# ESP_Client.net
KiCad netlist of a schematic drawn in EasyEDA
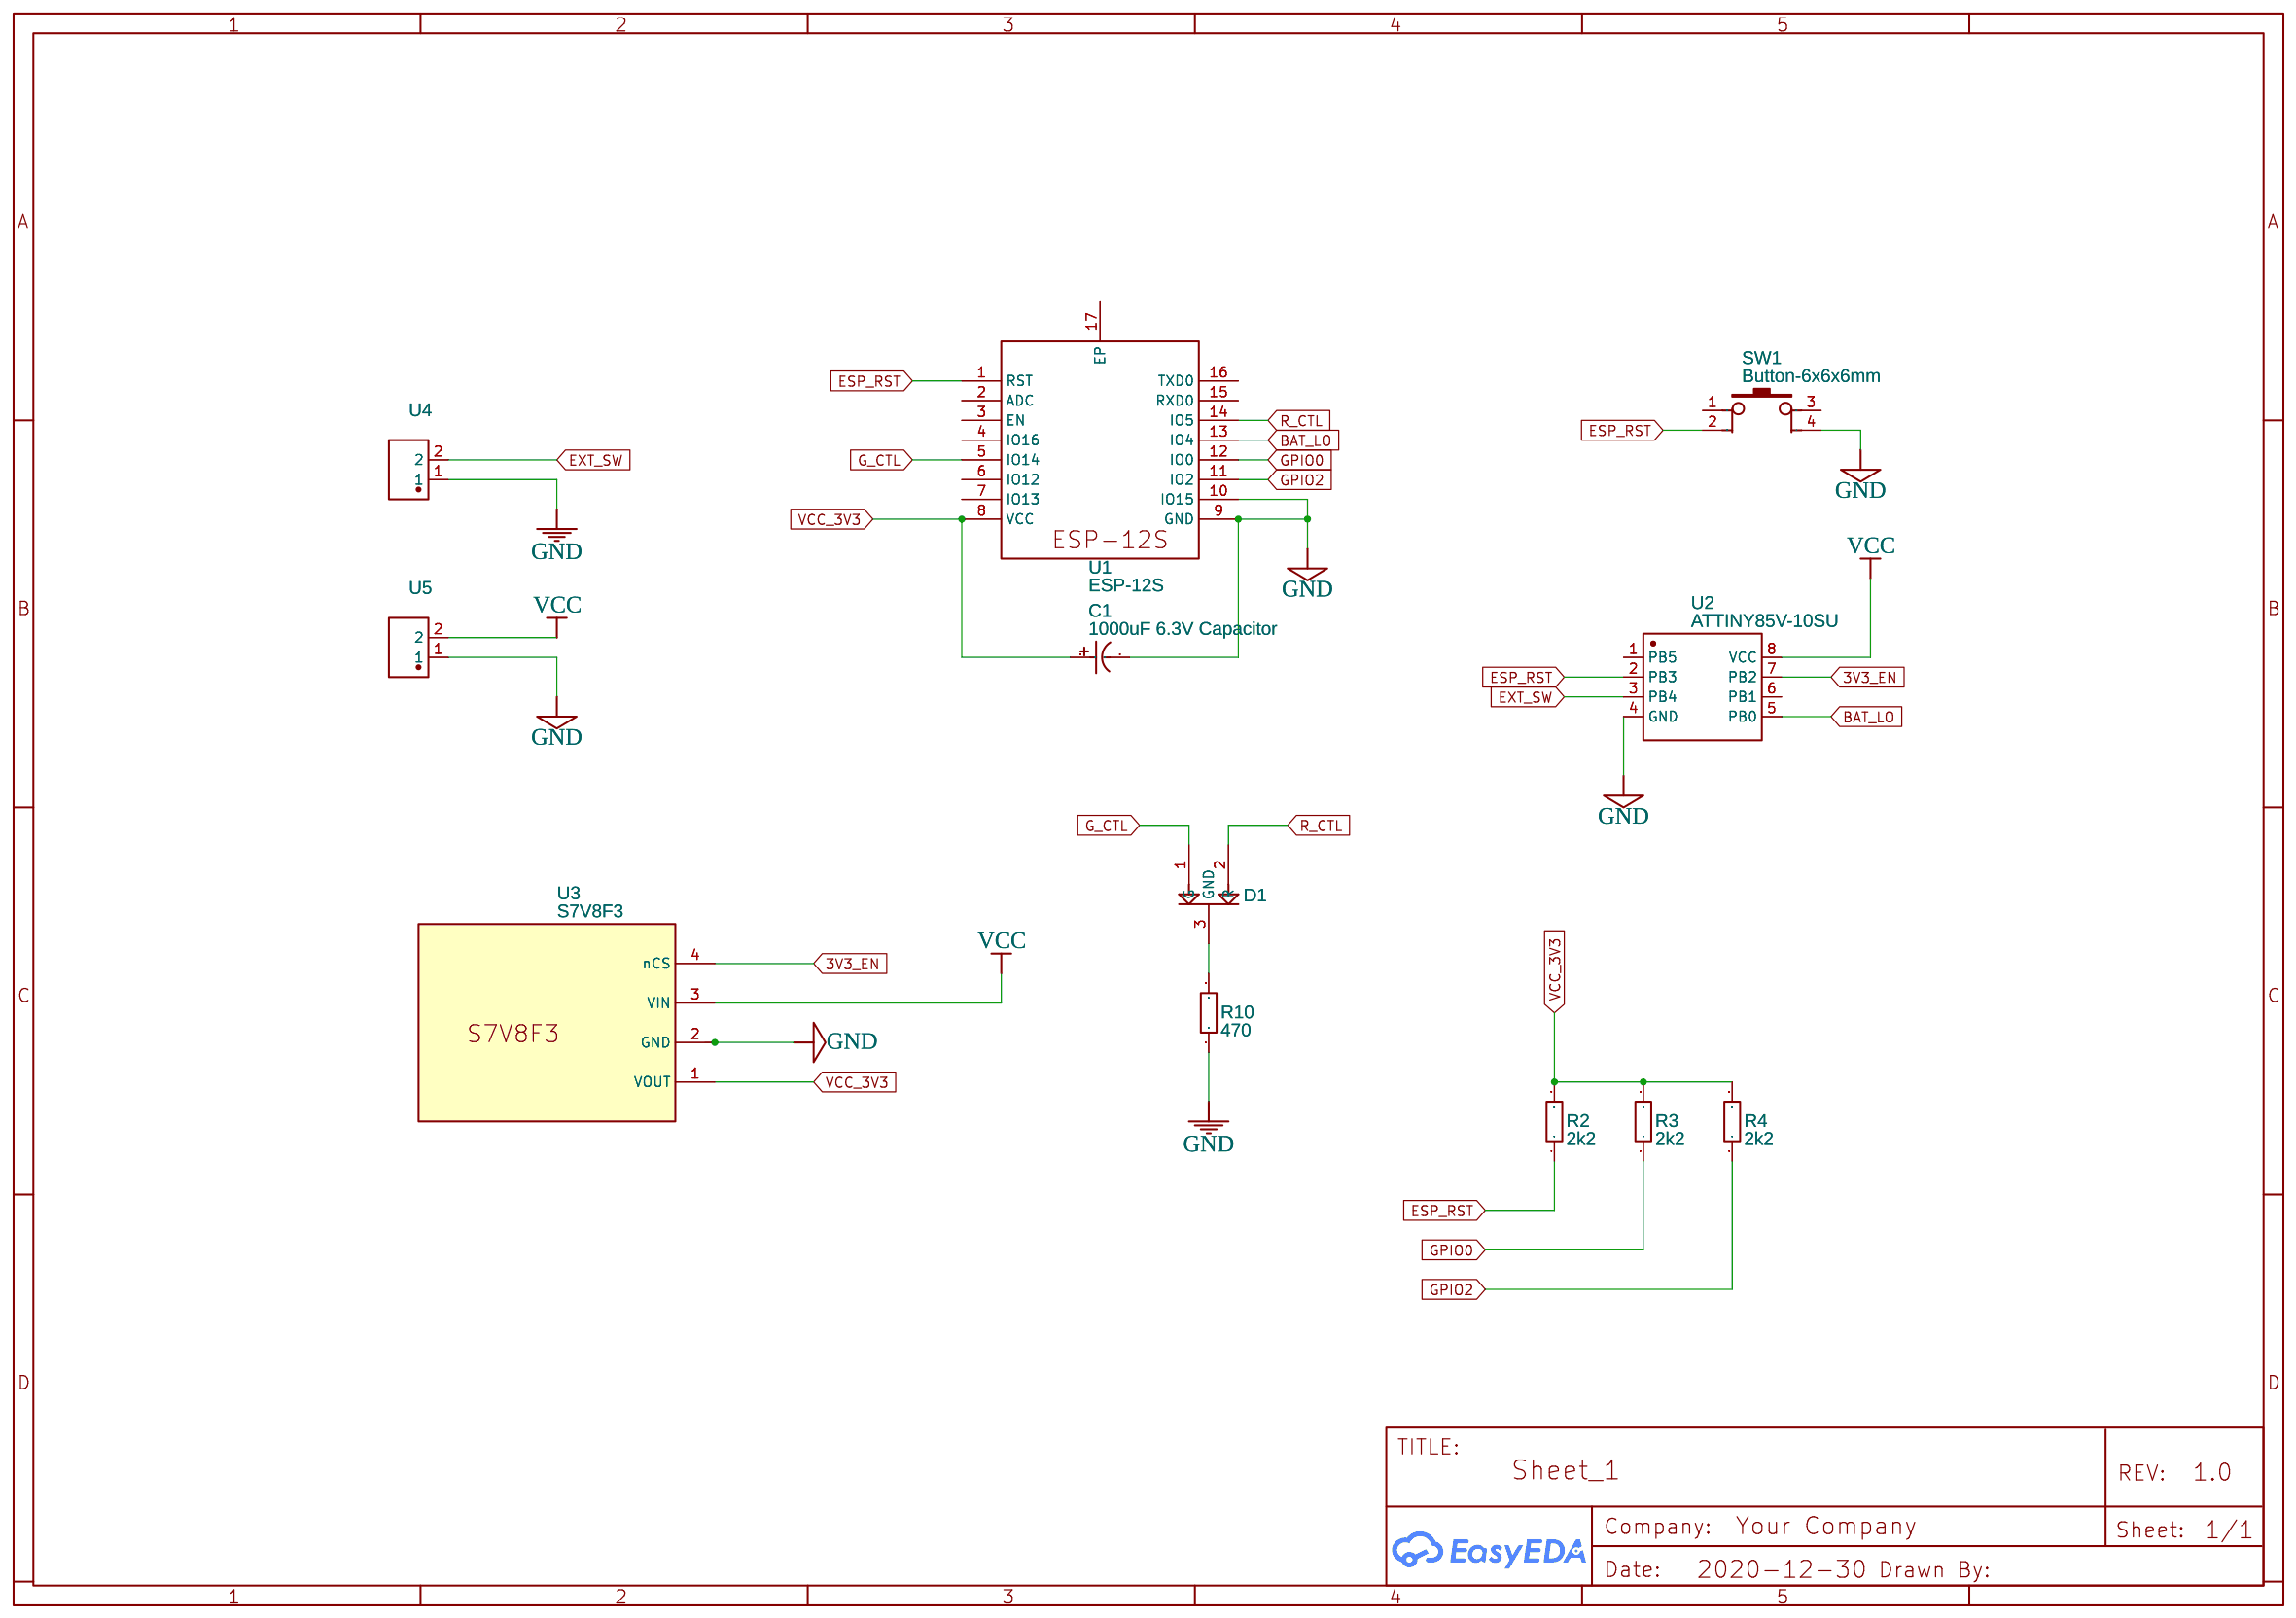
[diagram p0: schematic sheet]

(export (version "E")
  (design (tool "Eeschema 10.0.6"))
  (components
    (comp (ref "C1") (value "1000uF 6.3V Capacitor") (libsource (lib "") (part "1000uF 6.3V Capacitor")))
    (comp (ref "D1")
      (value "RED GREEN CATODO")
      (fields (field (name "BOM_Manufacturer Part") "RG309WK-C"))
      (libsource (lib "") (part "RED GREEN CATODO"))
    )
    (comp (ref "R2")
      (value "2k2")
      (fields
        (field (name "BOM_Manufacturer Part") "CFR02SJ0220A10")
        (field (name "BOM_Supplier Part") "C69874")
      )
      (libsource (lib "") (part "2k2"))
    )
    (comp (ref "R3")
      (value "2k2")
      (fields
        (field (name "BOM_Manufacturer Part") "CFR02SJ0220A10")
        (field (name "BOM_Supplier Part") "C69874")
      )
      (libsource (lib "") (part "2k2"))
    )
    (comp (ref "R4")
      (value "2k2")
      (fields
        (field (name "BOM_Manufacturer Part") "CFR02SJ0220A10")
        (field (name "BOM_Supplier Part") "C69874")
      )
      (libsource (lib "") (part "2k2"))
    )
    (comp (ref "R10")
      (value "470")
      (fields
        (field (name "BOM_Manufacturer Part") "MFR0W4F4700A50")
        (field (name "BOM_Supplier Part") "C58592")
      )
      (libsource (lib "") (part "47Ω"))
    )
    (comp (ref "SW1")
      (value "Button-6x6x6mm")
      (fields
        (field (name "BOM_Manufacturer Part") "Switch,6*6*6Plastic head,260G, 0.25mm,Straight line")
        (field (name "BOM_Supplier Part") "C71836")
      )
      (libsource (lib "") (part "Button-6x6x6mm"))
    )
    (comp (ref "U1")
      (value "ESP-12S")
      (fields (field (name "BOM_Supplier Part") "C82898"))
      (libsource (lib "") (part "ESP-12S"))
    )
    (comp (ref "U2")
      (value "ATTINY85V-10SU")
      (fields (field (name "BOM_Supplier Part") "C152192"))
      (libsource (lib "") (part "ATTINY85V-10SU"))
    )
    (comp (ref "U3") (value "S7V8F3") (libsource (lib "") (part "S7V8F3")))
    (comp (ref "U4")
      (value "XY301V-A-5.0-2P")
      (fields (field (name "BOM_Supplier Part") "C557651"))
      (libsource (lib "") (part "XY301V-A-5.0-2P"))
    )
    (comp (ref "U5")
      (value "XY301V-A-5.0-2P")
      (fields (field (name "BOM_Supplier Part") "C557651"))
      (libsource (lib "") (part "XY301V-A-5.0-2P"))
    )
  )
  (nets
    (net (code "1") (name "3V3_EN") (class "Default")
      (node (ref "U2") (pin "7") (pinfunction "PB2_7") (pintype "unspecified"))
      (node (ref "U3") (pin "4") (pinfunction "nCS_4") (pintype "unspecified"))
    )
    (net (code "2") (name "BAT_LO") (class "Default")
      (node (ref "U1") (pin "13") (pinfunction "IO4_13") (pintype "unspecified"))
      (node (ref "U2") (pin "5") (pinfunction "PB0_5") (pintype "unspecified"))
    )
    (net (code "3") (name "ESP_RST") (class "Default")
      (node (ref "R2") (pin "1") (pinfunction "1_1") (pintype "input"))
      (node (ref "SW1") (pin "2") (pinfunction "2_2") (pintype "input"))
      (node (ref "U1") (pin "1") (pinfunction "RST_1") (pintype "unspecified"))
      (node (ref "U2") (pin "2") (pinfunction "PB3_2") (pintype "unspecified"))
    )
    (net (code "4") (name "EXT_SW") (class "Default")
      (node (ref "U2") (pin "3") (pinfunction "PB4_3") (pintype "unspecified"))
      (node (ref "U4") (pin "2") (pinfunction "2_2") (pintype "unspecified"))
    )
    (net (code "5") (name "GND") (class "Default")
      (node (ref "C1") (pin "2") (pinfunction "2_2") (pintype "input"))
      (node (ref "R10") (pin "1") (pinfunction "1_1") (pintype "input"))
      (node (ref "SW1") (pin "4") (pinfunction "4_4") (pintype "input"))
      (node (ref "U1") (pin "10") (pinfunction "IO15_10") (pintype "unspecified"))
      (node (ref "U1") (pin "9") (pinfunction "GND_9") (pintype "unspecified"))
      (node (ref "U2") (pin "4") (pinfunction "GND_4") (pintype "unspecified"))
      (node (ref "U3") (pin "2") (pinfunction "GND_2") (pintype "unspecified"))
      (node (ref "U4") (pin "1") (pinfunction "1_1") (pintype "unspecified"))
      (node (ref "U5") (pin "1") (pinfunction "1_1") (pintype "unspecified"))
    )
    (net (code "6") (name "GPIO0") (class "Default")
      (node (ref "R3") (pin "1") (pinfunction "1_1") (pintype "input"))
      (node (ref "U1") (pin "12") (pinfunction "IO0_12") (pintype "unspecified"))
    )
    (net (code "7") (name "GPIO2") (class "Default")
      (node (ref "R4") (pin "1") (pinfunction "1_1") (pintype "input"))
      (node (ref "U1") (pin "11") (pinfunction "IO2_11") (pintype "unspecified"))
    )
    (net (code "8") (name "G_CTL") (class "Default")
      (node (ref "D1") (pin "1") (pinfunction "G_1") (pintype "unspecified"))
      (node (ref "U1") (pin "5") (pinfunction "IO14_5") (pintype "unspecified"))
    )
    (net (code "9") (name "Net-(D1-GND)") (class "Default")
      (node (ref "D1") (pin "3") (pinfunction "GND_3") (pintype "unspecified"))
      (node (ref "R10") (pin "2") (pinfunction "2_2") (pintype "input"))
    )
    (net (code "10") (name "R_CTL") (class "Default")
      (node (ref "D1") (pin "2") (pinfunction "R_2") (pintype "unspecified"))
      (node (ref "U1") (pin "14") (pinfunction "IO5_14") (pintype "unspecified"))
    )
    (net (code "11") (name "VCC") (class "Default")
      (node (ref "U2") (pin "8") (pinfunction "VCC_8") (pintype "unspecified"))
      (node (ref "U3") (pin "3") (pinfunction "VIN_3") (pintype "unspecified"))
      (node (ref "U5") (pin "2") (pinfunction "2_2") (pintype "unspecified"))
    )
    (net (code "12") (name "VCC_3V3") (class "Default")
      (node (ref "C1") (pin "1") (pinfunction "1_1") (pintype "input"))
      (node (ref "R2") (pin "2") (pinfunction "2_2") (pintype "input"))
      (node (ref "R3") (pin "2") (pinfunction "2_2") (pintype "input"))
      (node (ref "R4") (pin "2") (pinfunction "2_2") (pintype "input"))
      (node (ref "U1") (pin "8") (pinfunction "VCC_8") (pintype "unspecified"))
      (node (ref "U3") (pin "1") (pinfunction "VOUT_1") (pintype "unspecified"))
    )
    (net (code "13") (name "unconnected-(SW1-Pad1)") (class "Default")
      (node (ref "SW1") (pin "1") (pinfunction "1_1") (pintype "input"))
    )
    (net (code "14") (name "unconnected-(SW1-Pad3)") (class "Default")
      (node (ref "SW1") (pin "3") (pinfunction "3_3") (pintype "input"))
    )
    (net (code "15") (name "unconnected-(U1-ADC-Pad2)") (class "Default")
      (node (ref "U1") (pin "2") (pinfunction "ADC_2") (pintype "unspecified"))
    )
    (net (code "16") (name "unconnected-(U1-EN-Pad3)") (class "Default")
      (node (ref "U1") (pin "3") (pinfunction "EN_3") (pintype "unspecified"))
    )
    (net (code "17") (name "unconnected-(U1-EP-Pad17)") (class "Default")
      (node (ref "U1") (pin "17") (pinfunction "EP_17") (pintype "unspecified"))
    )
    (net (code "18") (name "unconnected-(U1-IO12-Pad6)") (class "Default")
      (node (ref "U1") (pin "6") (pinfunction "IO12_6") (pintype "unspecified"))
    )
    (net (code "19") (name "unconnected-(U1-IO13-Pad7)") (class "Default")
      (node (ref "U1") (pin "7") (pinfunction "IO13_7") (pintype "unspecified"))
    )
    (net (code "20") (name "unconnected-(U1-IO16-Pad4)") (class "Default")
      (node (ref "U1") (pin "4") (pinfunction "IO16_4") (pintype "unspecified"))
    )
    (net (code "21") (name "unconnected-(U1-RXD0-Pad15)") (class "Default")
      (node (ref "U1") (pin "15") (pinfunction "RXD0_15") (pintype "unspecified"))
    )
    (net (code "22") (name "unconnected-(U1-TXD0-Pad16)") (class "Default")
      (node (ref "U1") (pin "16") (pinfunction "TXD0_16") (pintype "unspecified"))
    )
    (net (code "23") (name "unconnected-(U2-PB1-Pad6)") (class "Default")
      (node (ref "U2") (pin "6") (pinfunction "PB1_6") (pintype "unspecified"))
    )
    (net (code "24") (name "unconnected-(U2-PB5-Pad1)") (class "Default")
      (node (ref "U2") (pin "1") (pinfunction "PB5_1") (pintype "unspecified"))
    )
  )
)
